# Board_A_Thumb_MOSFETs.net
KiCad netlist of a schematic drawn in Altium Designer
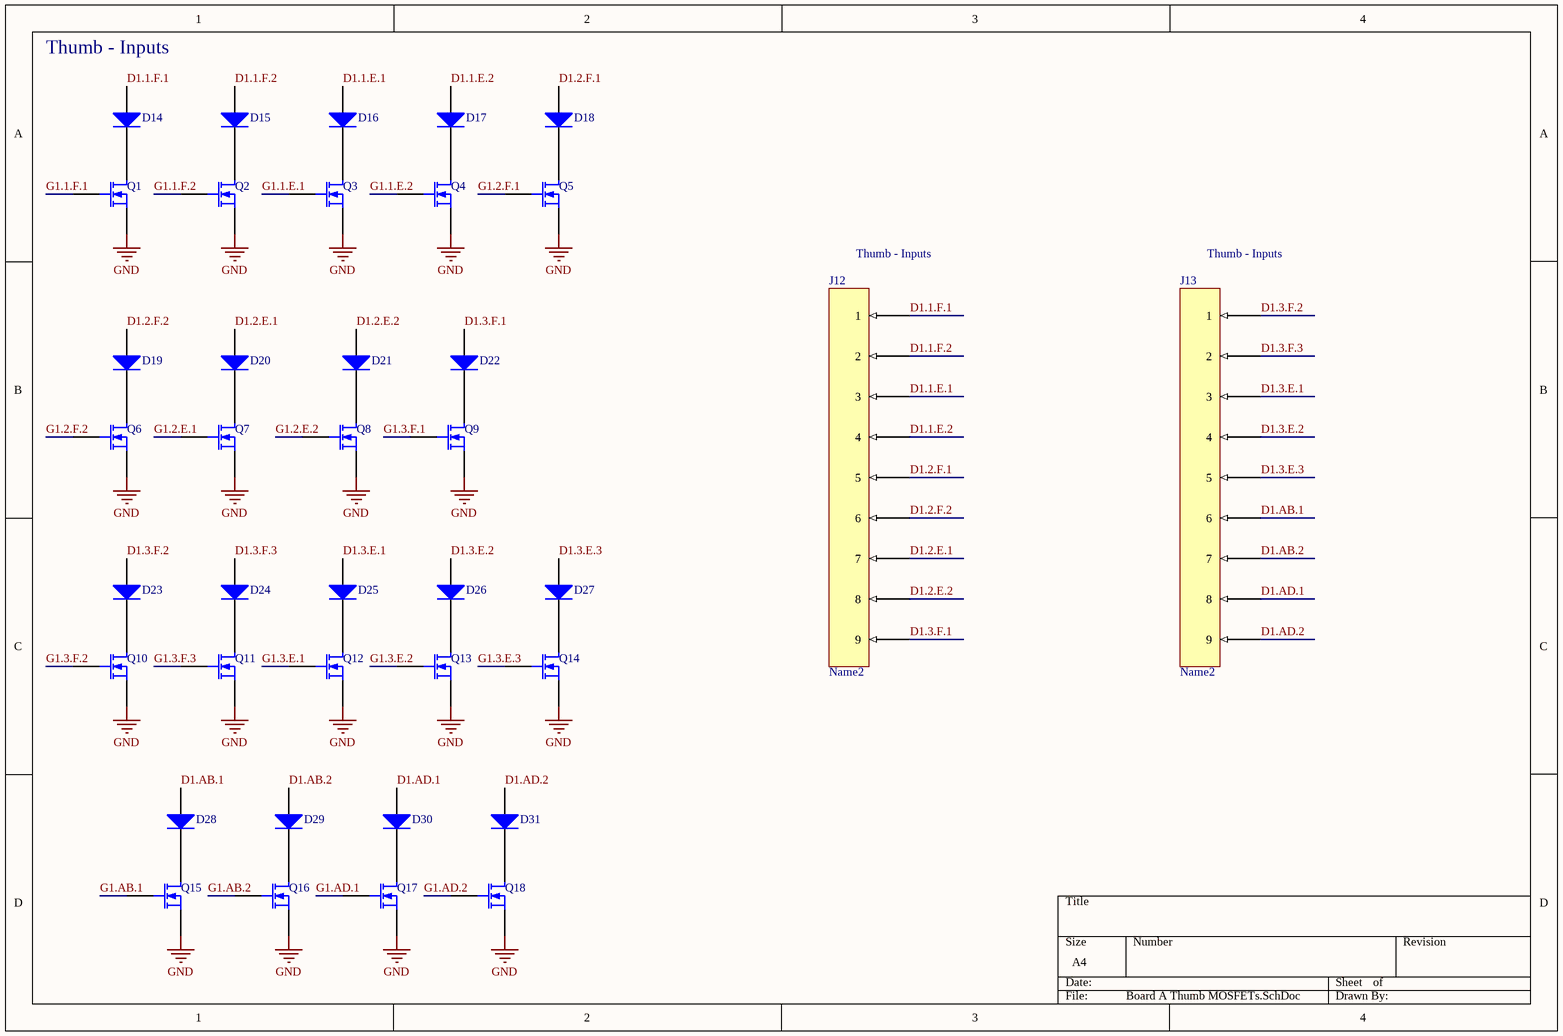
[diagram p0: Board A Thumb MOSFETs.SchDoc]

(export (version "E")
  (design (tool "Eeschema 10.0.6"))
  (components
    (comp (ref "D14")
      (value "de")
      (footprint "SMC")
      (description "Default Diode")
      (fields (field (name "PUBLISHER") "Altium Limited"))
      (libsource (lib "Miscellaneous Devices") (part "Diode"))
    )
    (comp (ref "D15")
      (value "de")
      (footprint "SMC")
      (description "Default Diode")
      (fields (field (name "PUBLISHER") "Altium Limited"))
      (libsource (lib "Miscellaneous Devices") (part "Diode"))
    )
    (comp (ref "D16")
      (value "de")
      (footprint "SMC")
      (description "Default Diode")
      (fields (field (name "PUBLISHER") "Altium Limited"))
      (libsource (lib "Miscellaneous Devices") (part "Diode"))
    )
    (comp (ref "D17")
      (value "de")
      (footprint "SMC")
      (description "Default Diode")
      (fields (field (name "PUBLISHER") "Altium Limited"))
      (libsource (lib "Miscellaneous Devices") (part "Diode"))
    )
    (comp (ref "D18")
      (value "de")
      (footprint "SMC")
      (description "Default Diode")
      (fields (field (name "PUBLISHER") "Altium Limited"))
      (libsource (lib "Miscellaneous Devices") (part "Diode"))
    )
    (comp (ref "D19")
      (value "de")
      (footprint "SMC")
      (description "Default Diode")
      (fields (field (name "PUBLISHER") "Altium Limited"))
      (libsource (lib "Miscellaneous Devices") (part "Diode"))
    )
    (comp (ref "D20")
      (value "de")
      (footprint "SMC")
      (description "Default Diode")
      (fields (field (name "PUBLISHER") "Altium Limited"))
      (libsource (lib "Miscellaneous Devices") (part "Diode"))
    )
    (comp (ref "D21")
      (value "de")
      (footprint "SMC")
      (description "Default Diode")
      (fields (field (name "PUBLISHER") "Altium Limited"))
      (libsource (lib "Miscellaneous Devices") (part "Diode"))
    )
    (comp (ref "D22")
      (value "de")
      (footprint "SMC")
      (description "Default Diode")
      (fields (field (name "PUBLISHER") "Altium Limited"))
      (libsource (lib "Miscellaneous Devices") (part "Diode"))
    )
    (comp (ref "D23")
      (value "de")
      (footprint "SMC")
      (description "Default Diode")
      (fields (field (name "PUBLISHER") "Altium Limited"))
      (libsource (lib "Miscellaneous Devices") (part "Diode"))
    )
    (comp (ref "D24")
      (value "de")
      (footprint "SMC")
      (description "Default Diode")
      (fields (field (name "PUBLISHER") "Altium Limited"))
      (libsource (lib "Miscellaneous Devices") (part "Diode"))
    )
    (comp (ref "D25")
      (value "de")
      (footprint "SMC")
      (description "Default Diode")
      (fields (field (name "PUBLISHER") "Altium Limited"))
      (libsource (lib "Miscellaneous Devices") (part "Diode"))
    )
    (comp (ref "D26")
      (value "de")
      (footprint "SMC")
      (description "Default Diode")
      (fields (field (name "PUBLISHER") "Altium Limited"))
      (libsource (lib "Miscellaneous Devices") (part "Diode"))
    )
    (comp (ref "D27")
      (value "de")
      (footprint "SMC")
      (description "Default Diode")
      (fields (field (name "PUBLISHER") "Altium Limited"))
      (libsource (lib "Miscellaneous Devices") (part "Diode"))
    )
    (comp (ref "D28")
      (value "de")
      (footprint "SMC")
      (description "Default Diode")
      (fields (field (name "PUBLISHER") "Altium Limited"))
      (libsource (lib "Miscellaneous Devices") (part "Diode"))
    )
    (comp (ref "D29")
      (value "de")
      (footprint "SMC")
      (description "Default Diode")
      (fields (field (name "PUBLISHER") "Altium Limited"))
      (libsource (lib "Miscellaneous Devices") (part "Diode"))
    )
    (comp (ref "D30")
      (value "de")
      (footprint "SMC")
      (description "Default Diode")
      (fields (field (name "PUBLISHER") "Altium Limited"))
      (libsource (lib "Miscellaneous Devices") (part "Diode"))
    )
    (comp (ref "D31")
      (value "de")
      (footprint "SMC")
      (description "Default Diode")
      (fields (field (name "PUBLISHER") "Altium Limited"))
      (libsource (lib "Miscellaneous Devices") (part "Diode"))
    )
    (comp (ref "J12")
      (value "Name2")
      (description "9 Position header")
      (libsource (lib "Schematics Library") (part "Name2"))
    )
    (comp (ref "J13")
      (value "Name2")
      (description "9 Position header")
      (libsource (lib "Schematics Library") (part "Name2"))
    )
    (comp (ref "Q1")
      (value "~")
      (description "N-Channel MOSFET")
      (fields (field (name "PUBLISHER") "Altium Limited"))
      (libsource (lib "Miscellaneous Devices") (part "MOSFET-N"))
    )
    (comp (ref "Q2")
      (value "~")
      (description "N-Channel MOSFET")
      (fields (field (name "PUBLISHER") "Altium Limited"))
      (libsource (lib "Miscellaneous Devices") (part "MOSFET-N"))
    )
    (comp (ref "Q3")
      (value "~")
      (description "N-Channel MOSFET")
      (fields (field (name "PUBLISHER") "Altium Limited"))
      (libsource (lib "Miscellaneous Devices") (part "MOSFET-N"))
    )
    (comp (ref "Q4")
      (value "~")
      (description "N-Channel MOSFET")
      (fields (field (name "PUBLISHER") "Altium Limited"))
      (libsource (lib "Miscellaneous Devices") (part "MOSFET-N"))
    )
    (comp (ref "Q5")
      (value "~")
      (description "N-Channel MOSFET")
      (fields (field (name "PUBLISHER") "Altium Limited"))
      (libsource (lib "Miscellaneous Devices") (part "MOSFET-N"))
    )
    (comp (ref "Q6")
      (value "~")
      (description "N-Channel MOSFET")
      (fields (field (name "PUBLISHER") "Altium Limited"))
      (libsource (lib "Miscellaneous Devices") (part "MOSFET-N"))
    )
    (comp (ref "Q7")
      (value "~")
      (description "N-Channel MOSFET")
      (fields (field (name "PUBLISHER") "Altium Limited"))
      (libsource (lib "Miscellaneous Devices") (part "MOSFET-N"))
    )
    (comp (ref "Q8")
      (value "~")
      (description "N-Channel MOSFET")
      (fields (field (name "PUBLISHER") "Altium Limited"))
      (libsource (lib "Miscellaneous Devices") (part "MOSFET-N"))
    )
    (comp (ref "Q9")
      (value "~")
      (description "N-Channel MOSFET")
      (fields (field (name "PUBLISHER") "Altium Limited"))
      (libsource (lib "Miscellaneous Devices") (part "MOSFET-N"))
    )
    (comp (ref "Q10")
      (value "~")
      (description "N-Channel MOSFET")
      (fields (field (name "PUBLISHER") "Altium Limited"))
      (libsource (lib "Miscellaneous Devices") (part "MOSFET-N"))
    )
    (comp (ref "Q11")
      (value "~")
      (description "N-Channel MOSFET")
      (fields (field (name "PUBLISHER") "Altium Limited"))
      (libsource (lib "Miscellaneous Devices") (part "MOSFET-N"))
    )
    (comp (ref "Q12")
      (value "~")
      (description "N-Channel MOSFET")
      (fields (field (name "PUBLISHER") "Altium Limited"))
      (libsource (lib "Miscellaneous Devices") (part "MOSFET-N"))
    )
    (comp (ref "Q13")
      (value "~")
      (description "N-Channel MOSFET")
      (fields (field (name "PUBLISHER") "Altium Limited"))
      (libsource (lib "Miscellaneous Devices") (part "MOSFET-N"))
    )
    (comp (ref "Q14")
      (value "~")
      (description "N-Channel MOSFET")
      (fields (field (name "PUBLISHER") "Altium Limited"))
      (libsource (lib "Miscellaneous Devices") (part "MOSFET-N"))
    )
    (comp (ref "Q15")
      (value "~")
      (description "N-Channel MOSFET")
      (fields (field (name "PUBLISHER") "Altium Limited"))
      (libsource (lib "Miscellaneous Devices") (part "MOSFET-N"))
    )
    (comp (ref "Q16")
      (value "~")
      (description "N-Channel MOSFET")
      (fields (field (name "PUBLISHER") "Altium Limited"))
      (libsource (lib "Miscellaneous Devices") (part "MOSFET-N"))
    )
    (comp (ref "Q17")
      (value "~")
      (description "N-Channel MOSFET")
      (fields (field (name "PUBLISHER") "Altium Limited"))
      (libsource (lib "Miscellaneous Devices") (part "MOSFET-N"))
    )
    (comp (ref "Q18")
      (value "~")
      (description "N-Channel MOSFET")
      (fields (field (name "PUBLISHER") "Altium Limited"))
      (libsource (lib "Miscellaneous Devices") (part "MOSFET-N"))
    )
  )
  (nets
    (net (code "1") (name "/D1.1.E.1") (class "Default")
      (node (ref "D16") (pin "1") (pinfunction "A_1") (pintype "passive"))
      (node (ref "J12") (pin "3") (pinfunction "3_3") (pintype "input"))
    )
    (net (code "2") (name "/D1.1.E.2") (class "Default")
      (node (ref "D17") (pin "1") (pinfunction "A_1") (pintype "passive"))
      (node (ref "J12") (pin "4") (pinfunction "4_4") (pintype "input"))
    )
    (net (code "3") (name "/D1.1.F.1") (class "Default")
      (node (ref "D14") (pin "1") (pinfunction "A_1") (pintype "passive"))
      (node (ref "J12") (pin "1") (pinfunction "1_1") (pintype "input"))
    )
    (net (code "4") (name "/D1.1.F.2") (class "Default")
      (node (ref "D15") (pin "1") (pinfunction "A_1") (pintype "passive"))
      (node (ref "J12") (pin "66") (pinfunction "2_66") (pintype "input"))
    )
    (net (code "5") (name "/D1.2.E.1") (class "Default")
      (node (ref "D20") (pin "1") (pinfunction "A_1") (pintype "passive"))
      (node (ref "J12") (pin "7") (pinfunction "7_7") (pintype "input"))
    )
    (net (code "6") (name "/D1.2.E.2") (class "Default")
      (node (ref "D21") (pin "1") (pinfunction "A_1") (pintype "passive"))
      (node (ref "J12") (pin "8") (pinfunction "8_8") (pintype "input"))
    )
    (net (code "7") (name "/D1.2.F.1") (class "Default")
      (node (ref "D18") (pin "1") (pinfunction "A_1") (pintype "passive"))
      (node (ref "J12") (pin "5") (pinfunction "5_5") (pintype "input"))
    )
    (net (code "8") (name "/D1.2.F.2") (class "Default")
      (node (ref "D19") (pin "1") (pinfunction "A_1") (pintype "passive"))
      (node (ref "J12") (pin "6") (pinfunction "6_6") (pintype "input"))
    )
    (net (code "9") (name "/D1.3.E.1") (class "Default")
      (node (ref "D25") (pin "1") (pinfunction "A_1") (pintype "passive"))
      (node (ref "J13") (pin "3") (pinfunction "3_3") (pintype "input"))
    )
    (net (code "10") (name "/D1.3.E.2") (class "Default")
      (node (ref "D26") (pin "1") (pinfunction "A_1") (pintype "passive"))
      (node (ref "J13") (pin "4") (pinfunction "4_4") (pintype "input"))
    )
    (net (code "11") (name "/D1.3.E.3") (class "Default")
      (node (ref "D27") (pin "1") (pinfunction "A_1") (pintype "passive"))
      (node (ref "J13") (pin "5") (pinfunction "5_5") (pintype "input"))
    )
    (net (code "12") (name "/D1.3.F.1") (class "Default")
      (node (ref "D22") (pin "1") (pinfunction "A_1") (pintype "passive"))
      (node (ref "J12") (pin "9") (pinfunction "9_9") (pintype "input"))
    )
    (net (code "13") (name "/D1.3.F.2") (class "Default")
      (node (ref "D23") (pin "1") (pinfunction "A_1") (pintype "passive"))
      (node (ref "J13") (pin "1") (pinfunction "1_1") (pintype "input"))
    )
    (net (code "14") (name "/D1.3.F.3") (class "Default")
      (node (ref "D24") (pin "1") (pinfunction "A_1") (pintype "passive"))
      (node (ref "J13") (pin "66") (pinfunction "2_66") (pintype "input"))
    )
    (net (code "15") (name "/D1.AB.1") (class "Default")
      (node (ref "D28") (pin "1") (pinfunction "A_1") (pintype "passive"))
      (node (ref "J13") (pin "6") (pinfunction "6_6") (pintype "input"))
    )
    (net (code "16") (name "/D1.AB.2") (class "Default")
      (node (ref "D29") (pin "1") (pinfunction "A_1") (pintype "passive"))
      (node (ref "J13") (pin "7") (pinfunction "7_7") (pintype "input"))
    )
    (net (code "17") (name "/D1.AD.1") (class "Default")
      (node (ref "D30") (pin "1") (pinfunction "A_1") (pintype "passive"))
      (node (ref "J13") (pin "8") (pinfunction "8_8") (pintype "input"))
    )
    (net (code "18") (name "/D1.AD.2") (class "Default")
      (node (ref "D31") (pin "1") (pinfunction "A_1") (pintype "passive"))
      (node (ref "J13") (pin "9") (pinfunction "9_9") (pintype "input"))
    )
    (net (code "19") (name "/G1.1.E.1") (class "Default")
      (node (ref "Q3") (pin "2") (pinfunction "G_2") (pintype "passive"))
    )
    (net (code "20") (name "/G1.1.E.2") (class "Default")
      (node (ref "Q4") (pin "2") (pinfunction "G_2") (pintype "passive"))
    )
    (net (code "21") (name "/G1.1.F.1") (class "Default")
      (node (ref "Q1") (pin "2") (pinfunction "G_2") (pintype "passive"))
    )
    (net (code "22") (name "/G1.1.F.2") (class "Default")
      (node (ref "Q2") (pin "2") (pinfunction "G_2") (pintype "passive"))
    )
    (net (code "23") (name "/G1.2.E.1") (class "Default")
      (node (ref "Q7") (pin "2") (pinfunction "G_2") (pintype "passive"))
    )
    (net (code "24") (name "/G1.2.E.2") (class "Default")
      (node (ref "Q8") (pin "2") (pinfunction "G_2") (pintype "passive"))
    )
    (net (code "25") (name "/G1.2.F.1") (class "Default")
      (node (ref "Q5") (pin "2") (pinfunction "G_2") (pintype "passive"))
    )
    (net (code "26") (name "/G1.2.F.2") (class "Default")
      (node (ref "Q6") (pin "2") (pinfunction "G_2") (pintype "passive"))
    )
    (net (code "27") (name "/G1.3.E.1") (class "Default")
      (node (ref "Q12") (pin "2") (pinfunction "G_2") (pintype "passive"))
    )
    (net (code "28") (name "/G1.3.E.2") (class "Default")
      (node (ref "Q13") (pin "2") (pinfunction "G_2") (pintype "passive"))
    )
    (net (code "29") (name "/G1.3.E.3") (class "Default")
      (node (ref "Q14") (pin "2") (pinfunction "G_2") (pintype "passive"))
    )
    (net (code "30") (name "/G1.3.F.1") (class "Default")
      (node (ref "Q9") (pin "2") (pinfunction "G_2") (pintype "passive"))
    )
    (net (code "31") (name "/G1.3.F.2") (class "Default")
      (node (ref "Q10") (pin "2") (pinfunction "G_2") (pintype "passive"))
    )
    (net (code "32") (name "/G1.3.F.3") (class "Default")
      (node (ref "Q11") (pin "2") (pinfunction "G_2") (pintype "passive"))
    )
    (net (code "33") (name "/G1.AB.1") (class "Default")
      (node (ref "Q15") (pin "2") (pinfunction "G_2") (pintype "passive"))
    )
    (net (code "34") (name "/G1.AB.2") (class "Default")
      (node (ref "Q16") (pin "2") (pinfunction "G_2") (pintype "passive"))
    )
    (net (code "35") (name "/G1.AD.1") (class "Default")
      (node (ref "Q17") (pin "2") (pinfunction "G_2") (pintype "passive"))
    )
    (net (code "36") (name "/G1.AD.2") (class "Default")
      (node (ref "Q18") (pin "2") (pinfunction "G_2") (pintype "passive"))
    )
    (net (code "37") (name "GND") (class "Default")
      (node (ref "Q1") (pin "3") (pinfunction "S_3") (pintype "passive"))
      (node (ref "Q10") (pin "3") (pinfunction "S_3") (pintype "passive"))
      (node (ref "Q11") (pin "3") (pinfunction "S_3") (pintype "passive"))
      (node (ref "Q12") (pin "3") (pinfunction "S_3") (pintype "passive"))
      (node (ref "Q13") (pin "3") (pinfunction "S_3") (pintype "passive"))
      (node (ref "Q14") (pin "3") (pinfunction "S_3") (pintype "passive"))
      (node (ref "Q15") (pin "3") (pinfunction "S_3") (pintype "passive"))
      (node (ref "Q16") (pin "3") (pinfunction "S_3") (pintype "passive"))
      (node (ref "Q17") (pin "3") (pinfunction "S_3") (pintype "passive"))
      (node (ref "Q18") (pin "3") (pinfunction "S_3") (pintype "passive"))
      (node (ref "Q2") (pin "3") (pinfunction "S_3") (pintype "passive"))
      (node (ref "Q3") (pin "3") (pinfunction "S_3") (pintype "passive"))
      (node (ref "Q4") (pin "3") (pinfunction "S_3") (pintype "passive"))
      (node (ref "Q5") (pin "3") (pinfunction "S_3") (pintype "passive"))
      (node (ref "Q6") (pin "3") (pinfunction "S_3") (pintype "passive"))
      (node (ref "Q7") (pin "3") (pinfunction "S_3") (pintype "passive"))
      (node (ref "Q8") (pin "3") (pinfunction "S_3") (pintype "passive"))
      (node (ref "Q9") (pin "3") (pinfunction "S_3") (pintype "passive"))
    )
    (net (code "38") (name "Net-(D14-K)") (class "Default")
      (node (ref "D14") (pin "2") (pinfunction "K_2") (pintype "passive"))
      (node (ref "Q1") (pin "1") (pinfunction "D_1") (pintype "passive"))
    )
    (net (code "39") (name "Net-(D15-K)") (class "Default")
      (node (ref "D15") (pin "2") (pinfunction "K_2") (pintype "passive"))
      (node (ref "Q2") (pin "1") (pinfunction "D_1") (pintype "passive"))
    )
    (net (code "40") (name "Net-(D16-K)") (class "Default")
      (node (ref "D16") (pin "2") (pinfunction "K_2") (pintype "passive"))
      (node (ref "Q3") (pin "1") (pinfunction "D_1") (pintype "passive"))
    )
    (net (code "41") (name "Net-(D17-K)") (class "Default")
      (node (ref "D17") (pin "2") (pinfunction "K_2") (pintype "passive"))
      (node (ref "Q4") (pin "1") (pinfunction "D_1") (pintype "passive"))
    )
    (net (code "42") (name "Net-(D18-K)") (class "Default")
      (node (ref "D18") (pin "2") (pinfunction "K_2") (pintype "passive"))
      (node (ref "Q5") (pin "1") (pinfunction "D_1") (pintype "passive"))
    )
    (net (code "43") (name "Net-(D19-K)") (class "Default")
      (node (ref "D19") (pin "2") (pinfunction "K_2") (pintype "passive"))
      (node (ref "Q6") (pin "1") (pinfunction "D_1") (pintype "passive"))
    )
    (net (code "44") (name "Net-(D20-K)") (class "Default")
      (node (ref "D20") (pin "2") (pinfunction "K_2") (pintype "passive"))
      (node (ref "Q7") (pin "1") (pinfunction "D_1") (pintype "passive"))
    )
    (net (code "45") (name "Net-(D21-K)") (class "Default")
      (node (ref "D21") (pin "2") (pinfunction "K_2") (pintype "passive"))
      (node (ref "Q8") (pin "1") (pinfunction "D_1") (pintype "passive"))
    )
    (net (code "46") (name "Net-(D22-K)") (class "Default")
      (node (ref "D22") (pin "2") (pinfunction "K_2") (pintype "passive"))
      (node (ref "Q9") (pin "1") (pinfunction "D_1") (pintype "passive"))
    )
    (net (code "47") (name "Net-(D23-K)") (class "Default")
      (node (ref "D23") (pin "2") (pinfunction "K_2") (pintype "passive"))
      (node (ref "Q10") (pin "1") (pinfunction "D_1") (pintype "passive"))
    )
    (net (code "48") (name "Net-(D24-K)") (class "Default")
      (node (ref "D24") (pin "2") (pinfunction "K_2") (pintype "passive"))
      (node (ref "Q11") (pin "1") (pinfunction "D_1") (pintype "passive"))
    )
    (net (code "49") (name "Net-(D25-K)") (class "Default")
      (node (ref "D25") (pin "2") (pinfunction "K_2") (pintype "passive"))
      (node (ref "Q12") (pin "1") (pinfunction "D_1") (pintype "passive"))
    )
    (net (code "50") (name "Net-(D26-K)") (class "Default")
      (node (ref "D26") (pin "2") (pinfunction "K_2") (pintype "passive"))
      (node (ref "Q13") (pin "1") (pinfunction "D_1") (pintype "passive"))
    )
    (net (code "51") (name "Net-(D27-K)") (class "Default")
      (node (ref "D27") (pin "2") (pinfunction "K_2") (pintype "passive"))
      (node (ref "Q14") (pin "1") (pinfunction "D_1") (pintype "passive"))
    )
    (net (code "52") (name "Net-(D28-K)") (class "Default")
      (node (ref "D28") (pin "2") (pinfunction "K_2") (pintype "passive"))
      (node (ref "Q15") (pin "1") (pinfunction "D_1") (pintype "passive"))
    )
    (net (code "53") (name "Net-(D29-K)") (class "Default")
      (node (ref "D29") (pin "2") (pinfunction "K_2") (pintype "passive"))
      (node (ref "Q16") (pin "1") (pinfunction "D_1") (pintype "passive"))
    )
    (net (code "54") (name "Net-(D30-K)") (class "Default")
      (node (ref "D30") (pin "2") (pinfunction "K_2") (pintype "passive"))
      (node (ref "Q17") (pin "1") (pinfunction "D_1") (pintype "passive"))
    )
    (net (code "55") (name "Net-(D31-K)") (class "Default")
      (node (ref "D31") (pin "2") (pinfunction "K_2") (pintype "passive"))
      (node (ref "Q18") (pin "1") (pinfunction "D_1") (pintype "passive"))
    )
  )
)
